# MainBoard.net
KiCad netlist of a schematic drawn in EAGLE
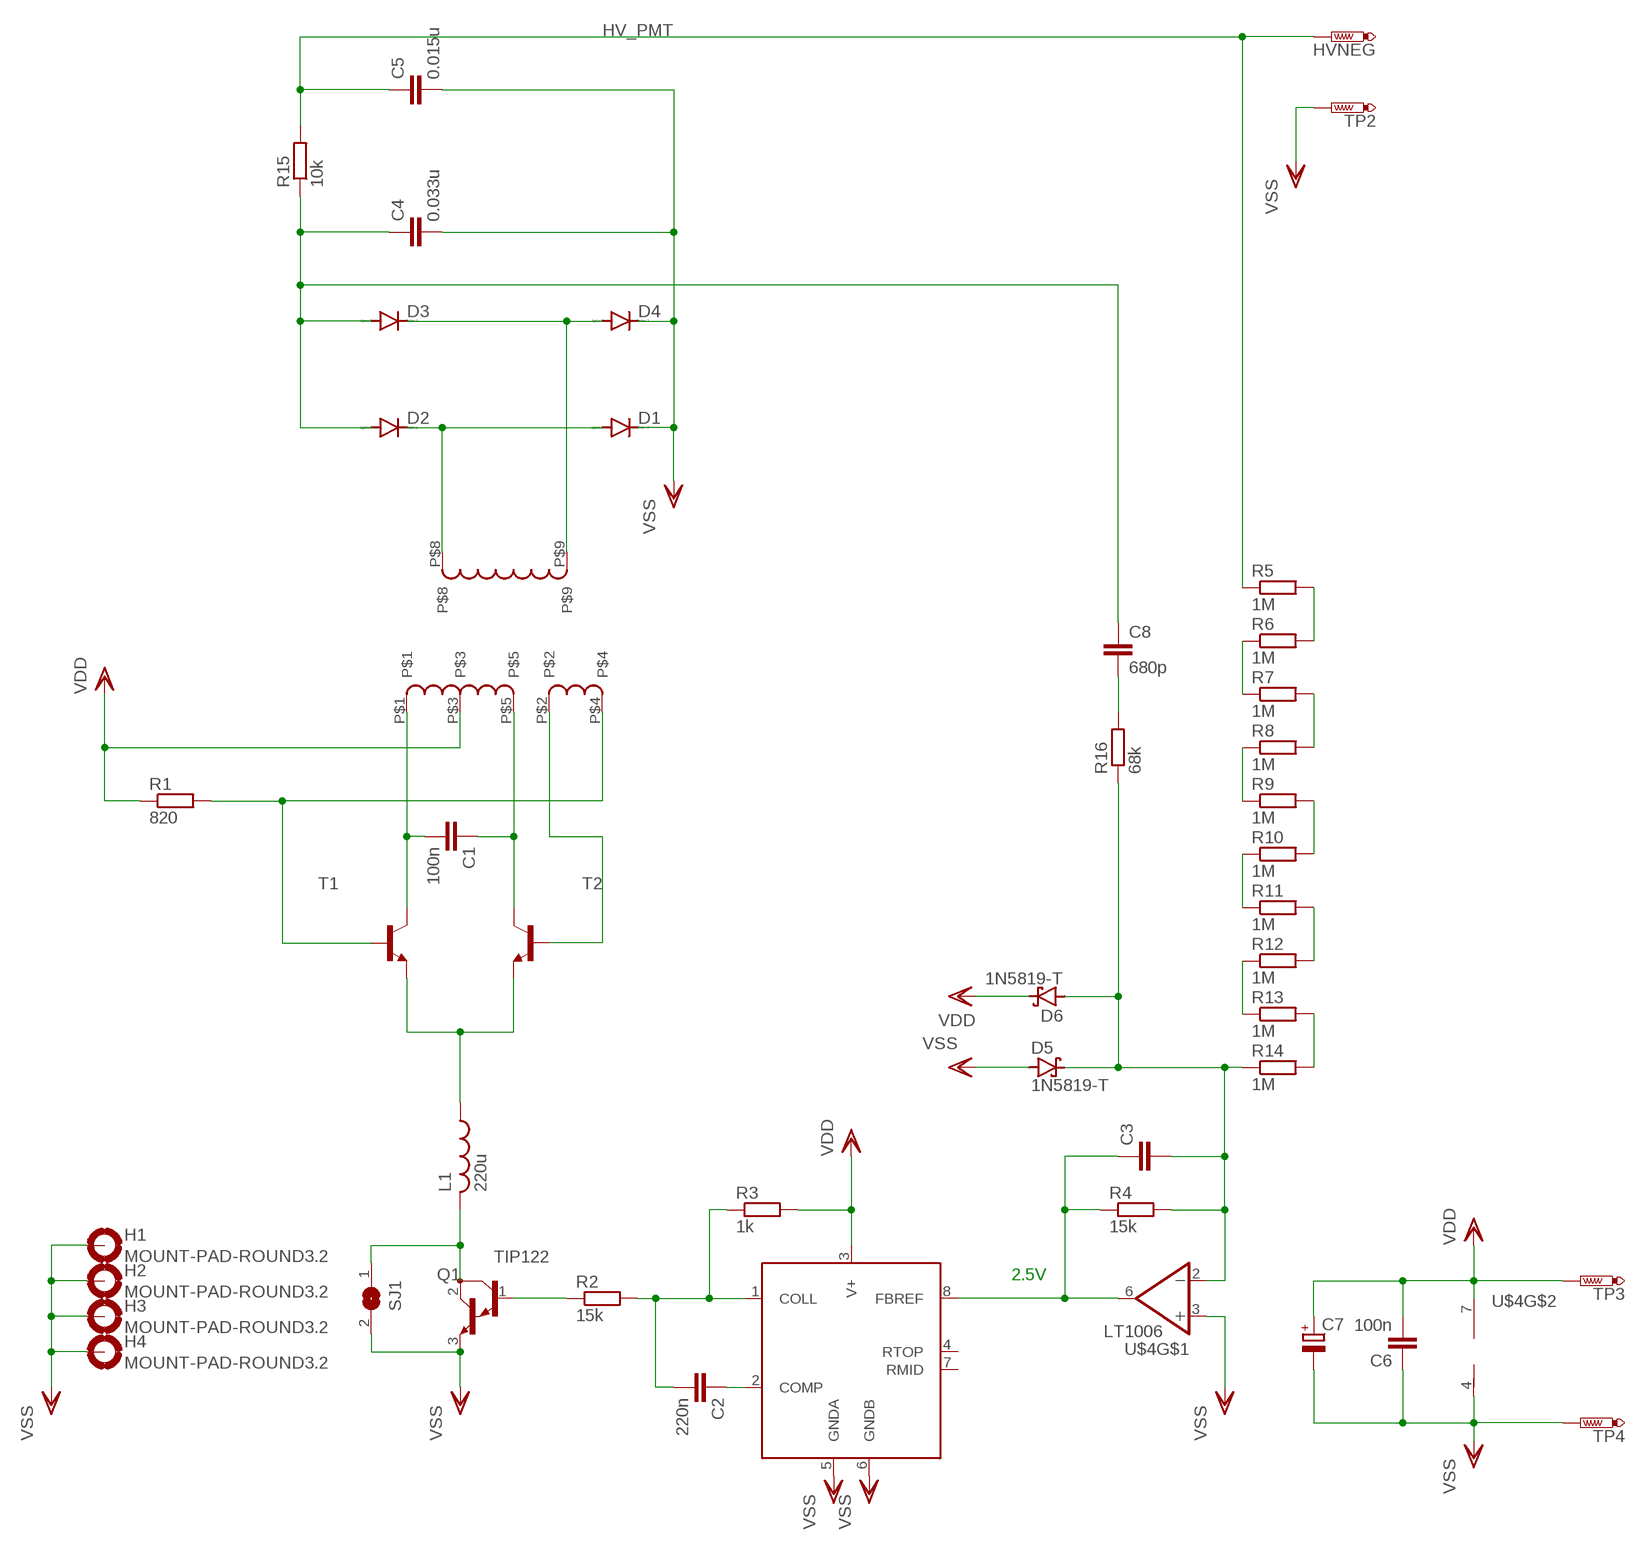
[diagram p0: schematic, sheet 1]

(export (version "E")
  (design (tool "Eeschema 10.0.6"))
  (components
    (comp (ref "C1")
      (value "100n")
      (footprint "eagle-import:C075-032X103")
      (libsource (lib "eagle-import") (part "C-EU075-032X103"))
    )
    (comp (ref "C2")
      (value "220n")
      (footprint "eagle-import:C050-035X075")
      (libsource (lib "eagle-import") (part "C-EU050-035X075"))
    )
    (comp (ref "C3")
      (value "C-EU075-032X103")
      (footprint "eagle-import:C075-032X103")
      (libsource (lib "eagle-import") (part "C-EU075-032X103"))
    )
    (comp (ref "C4")
      (value "0.033u")
      (footprint "eagle-import:C225-087X268")
      (libsource (lib "eagle-import") (part "C-EU225-087X268"))
    )
    (comp (ref "C5")
      (value "0.015u")
      (footprint "eagle-import:C225-087X268")
      (libsource (lib "eagle-import") (part "C-EU225-087X268"))
    )
    (comp (ref "C6")
      (value "100n")
      (footprint "eagle-import:C075-032X103")
      (libsource (lib "eagle-import") (part "C-EU075-032X103"))
    )
    (comp (ref "C7")
      (value "CPOL-EUE2.5-7")
      (footprint "eagle-import:E2,5-7")
      (libsource (lib "eagle-import") (part "CPOL-EUE2.5-7"))
    )
    (comp (ref "C8")
      (value "680p")
      (footprint "eagle-import:C150-064X183")
      (libsource (lib "eagle-import") (part "C-EU150-064X183"))
    )
    (comp (ref "D1")
      (value "DIODE-DO41-10")
      (footprint "eagle-import:DO41-10")
      (libsource (lib "eagle-import") (part "DIODE-DO41-10"))
    )
    (comp (ref "D2")
      (value "DIODE-DO41-10")
      (footprint "eagle-import:DO41-10")
      (libsource (lib "eagle-import") (part "DIODE-DO41-10"))
    )
    (comp (ref "D3")
      (value "DIODE-DO41-10")
      (footprint "eagle-import:DO41-10")
      (libsource (lib "eagle-import") (part "DIODE-DO41-10"))
    )
    (comp (ref "D4")
      (value "DIODE-DO41-10")
      (footprint "eagle-import:DO41-10")
      (libsource (lib "eagle-import") (part "DIODE-DO41-10"))
    )
    (comp (ref "D5")
      (value "1N5819-T")
      (footprint "eagle-import:DO41-7.6")
      (libsource (lib "eagle-import") (part "1N5819-T"))
    )
    (comp (ref "D6")
      (value "1N5819-T")
      (footprint "eagle-import:DO41-7.6")
      (libsource (lib "eagle-import") (part "1N5819-T"))
    )
    (comp (ref "H1")
      (value "MOUNT-PAD-ROUND3.2")
      (footprint "eagle-import:3,2-PAD")
      (libsource (lib "eagle-import") (part "MOUNT-PAD-ROUND3.2"))
    )
    (comp (ref "H2")
      (value "MOUNT-PAD-ROUND3.2")
      (footprint "eagle-import:3,2-PAD")
      (libsource (lib "eagle-import") (part "MOUNT-PAD-ROUND3.2"))
    )
    (comp (ref "H3")
      (value "MOUNT-PAD-ROUND3.2")
      (footprint "eagle-import:3,2-PAD")
      (libsource (lib "eagle-import") (part "MOUNT-PAD-ROUND3.2"))
    )
    (comp (ref "H4")
      (value "MOUNT-PAD-ROUND3.2")
      (footprint "eagle-import:3,2-PAD")
      (libsource (lib "eagle-import") (part "MOUNT-PAD-ROUND3.2"))
    )
    (comp (ref "HVNEG")
      (value "PTR1PAD1-13Y")
      (footprint "eagle-import:P1-13Y")
      (libsource (lib "eagle-import") (part "PTR1PAD1-13Y"))
    )
    (comp (ref "L1")
      (value "220u")
      (footprint "eagle-import:0207_15")
      (libsource (lib "eagle-import") (part "L-US0207/15"))
    )
    (comp (ref "Q1")
      (value "TIP122")
      (footprint "eagle-import:TO220")
      (libsource (lib "eagle-import") (part "TIP122"))
    )
    (comp (ref "R1")
      (value "820")
      (footprint "eagle-import:0207_7")
      (libsource (lib "eagle-import") (part "R-EU_0207/7"))
    )
    (comp (ref "R2")
      (value "15k")
      (footprint "eagle-import:0207_7")
      (libsource (lib "eagle-import") (part "R-EU_0207/7"))
    )
    (comp (ref "R3")
      (value "1k")
      (footprint "eagle-import:0207_7")
      (libsource (lib "eagle-import") (part "R-EU_0207/7"))
    )
    (comp (ref "R4")
      (value "15k")
      (footprint "eagle-import:0207_7")
      (libsource (lib "eagle-import") (part "R-EU_0207/7"))
    )
    (comp (ref "R5")
      (value "1M")
      (footprint "eagle-import:0207_7")
      (libsource (lib "eagle-import") (part "R-EU_0207/7"))
    )
    (comp (ref "R6")
      (value "1M")
      (footprint "eagle-import:0207_7")
      (libsource (lib "eagle-import") (part "R-EU_0207/7"))
    )
    (comp (ref "R7")
      (value "1M")
      (footprint "eagle-import:0207_7")
      (libsource (lib "eagle-import") (part "R-EU_0207/7"))
    )
    (comp (ref "R8")
      (value "1M")
      (footprint "eagle-import:0207_7")
      (libsource (lib "eagle-import") (part "R-EU_0207/7"))
    )
    (comp (ref "R9")
      (value "1M")
      (footprint "eagle-import:0207_7")
      (libsource (lib "eagle-import") (part "R-EU_0207/7"))
    )
    (comp (ref "R10")
      (value "1M")
      (footprint "eagle-import:0207_7")
      (libsource (lib "eagle-import") (part "R-EU_0207/7"))
    )
    (comp (ref "R11")
      (value "1M")
      (footprint "eagle-import:0207_7")
      (libsource (lib "eagle-import") (part "R-EU_0207/7"))
    )
    (comp (ref "R12")
      (value "1M")
      (footprint "eagle-import:0207_7")
      (libsource (lib "eagle-import") (part "R-EU_0207/7"))
    )
    (comp (ref "R13")
      (value "1M")
      (footprint "eagle-import:0207_7")
      (libsource (lib "eagle-import") (part "R-EU_0207/7"))
    )
    (comp (ref "R14")
      (value "1M")
      (footprint "eagle-import:0207_7")
      (libsource (lib "eagle-import") (part "R-EU_0207/7"))
    )
    (comp (ref "R15")
      (value "10k")
      (footprint "eagle-import:0207_7")
      (libsource (lib "eagle-import") (part "R-EU_0207/7"))
    )
    (comp (ref "R16")
      (value "68k")
      (footprint "eagle-import:0207_7")
      (libsource (lib "eagle-import") (part "R-EU_0207/7"))
    )
    (comp (ref "SJ1") (value "SJ") (footprint "eagle-import:SJ") (libsource (lib "eagle-import") (part "SJ")))
    (comp (ref "T1")
      (value "-NPN-TO92-EBC")
      (footprint "eagle-import:TO92-EBC")
      (libsource (lib "eagle-import") (part "-NPN-TO92-EBC"))
    )
    (comp (ref "T2")
      (value "-NPN-TO92-EBC")
      (footprint "eagle-import:TO92-EBC")
      (libsource (lib "eagle-import") (part "-NPN-TO92-EBC"))
    )
    (comp (ref "TP2")
      (value "PTR1PAD1-13Y")
      (footprint "eagle-import:P1-13Y")
      (libsource (lib "eagle-import") (part "PTR1PAD1-13Y"))
    )
    (comp (ref "TP3")
      (value "PTR1PAD1-13Y")
      (footprint "eagle-import:P1-13Y")
      (libsource (lib "eagle-import") (part "PTR1PAD1-13Y"))
    )
    (comp (ref "TP4")
      (value "PTR1PAD1-13Y")
      (footprint "eagle-import:P1-13Y")
      (libsource (lib "eagle-import") (part "PTR1PAD1-13Y"))
    )
    (comp (ref "U$1")
      (value "FL2015")
      (footprint "eagle-import:FL2015-A")
      (libsource (lib "eagle-import") (part "FL2015"))
    )
    (comp (ref "U$3")
      (value "LT1431")
      (footprint "eagle-import:SO08")
      (libsource (lib "eagle-import") (part "LT1431"))
    )
    (comp (ref "U$4")
      (value "LT1006")
      (footprint "eagle-import:SO08")
      (libsource (lib "eagle-import") (part "LT1006"))
    )
  )
  (nets
    (net (code "1") (name "/HV_PMT") (class "Default")
      (node (ref "C5") (pin "1") (pinfunction "1_1") (pintype "passive"))
      (node (ref "HVNEG") (pin "TP") (pinfunction "TP_TP") (pintype "input"))
      (node (ref "R15") (pin "2") (pinfunction "2_2") (pintype "passive"))
      (node (ref "R5") (pin "1") (pinfunction "1_1") (pintype "passive"))
    )
    (net (code "2") (name "Net-(C1-Pad1)") (class "Default")
      (node (ref "C1") (pin "1") (pinfunction "1_1") (pintype "passive"))
      (node (ref "T2") (pin "C") (pinfunction "C_C") (pintype "passive"))
      (node (ref "U$1") (pin "P$5") (pinfunction "P$5_P$5") (pintype "bidirectional"))
    )
    (net (code "3") (name "Net-(C1-Pad2)") (class "Default")
      (node (ref "C1") (pin "2") (pinfunction "2_2") (pintype "passive"))
      (node (ref "T1") (pin "C") (pinfunction "C_C") (pintype "passive"))
      (node (ref "U$1") (pin "P$1") (pinfunction "P$1_P$1") (pintype "bidirectional"))
    )
    (net (code "4") (name "Net-(C4-Pad1)") (class "Default")
      (node (ref "C4") (pin "1") (pinfunction "1_1") (pintype "passive"))
      (node (ref "C8") (pin "1") (pinfunction "1_1") (pintype "passive"))
      (node (ref "D2") (pin "A") (pinfunction "A_A") (pintype "passive"))
      (node (ref "D3") (pin "A") (pinfunction "A_A") (pintype "passive"))
      (node (ref "R15") (pin "1") (pinfunction "1_1") (pintype "passive"))
    )
    (net (code "5") (name "Net-(C8-Pad2)") (class "Default")
      (node (ref "C8") (pin "2") (pinfunction "2_2") (pintype "passive"))
      (node (ref "R16") (pin "2") (pinfunction "2_2") (pintype "passive"))
    )
    (net (code "6") (name "Net-(D1-PadA)") (class "Default")
      (node (ref "D1") (pin "A") (pinfunction "A_A") (pintype "passive"))
      (node (ref "D2") (pin "C") (pinfunction "C_C") (pintype "passive"))
      (node (ref "U$1") (pin "P$8") (pinfunction "P$8_P$8") (pintype "bidirectional"))
    )
    (net (code "7") (name "Net-(D3-PadC)") (class "Default")
      (node (ref "D3") (pin "C") (pinfunction "C_C") (pintype "passive"))
      (node (ref "D4") (pin "A") (pinfunction "A_A") (pintype "passive"))
      (node (ref "U$1") (pin "P$9") (pinfunction "P$9_P$9") (pintype "bidirectional"))
    )
    (net (code "8") (name "Net-(L1-Pad1)") (class "Default")
      (node (ref "L1") (pin "1") (pinfunction "1_1") (pintype "passive"))
      (node (ref "T1") (pin "E") (pinfunction "E_E") (pintype "passive"))
      (node (ref "T2") (pin "E") (pinfunction "E_E") (pintype "passive"))
    )
    (net (code "9") (name "Net-(Q1-B)") (class "Default")
      (node (ref "Q1") (pin "1") (pinfunction "B_1") (pintype "passive"))
      (node (ref "R2") (pin "1") (pinfunction "1_1") (pintype "passive"))
    )
    (net (code "10") (name "Net-(Q1-C)") (class "Default")
      (node (ref "L1") (pin "2") (pinfunction "2_2") (pintype "passive"))
      (node (ref "Q1") (pin "2") (pinfunction "C_2") (pintype "passive"))
      (node (ref "SJ1") (pin "1") (pinfunction "1_1") (pintype "passive"))
    )
    (net (code "11") (name "Net-(R1-Pad2)") (class "Default")
      (node (ref "R1") (pin "2") (pinfunction "2_2") (pintype "passive"))
      (node (ref "T1") (pin "B") (pinfunction "B_B") (pintype "passive"))
      (node (ref "U$1") (pin "P$4") (pinfunction "P$4_P$4") (pintype "bidirectional"))
    )
    (net (code "12") (name "Net-(R5-Pad2)") (class "Default")
      (node (ref "R5") (pin "2") (pinfunction "2_2") (pintype "passive"))
      (node (ref "R6") (pin "2") (pinfunction "2_2") (pintype "passive"))
    )
    (net (code "13") (name "Net-(R6-Pad1)") (class "Default")
      (node (ref "R6") (pin "1") (pinfunction "1_1") (pintype "passive"))
      (node (ref "R7") (pin "1") (pinfunction "1_1") (pintype "passive"))
    )
    (net (code "14") (name "Net-(R7-Pad2)") (class "Default")
      (node (ref "R7") (pin "2") (pinfunction "2_2") (pintype "passive"))
      (node (ref "R8") (pin "2") (pinfunction "2_2") (pintype "passive"))
    )
    (net (code "15") (name "Net-(R8-Pad1)") (class "Default")
      (node (ref "R8") (pin "1") (pinfunction "1_1") (pintype "passive"))
      (node (ref "R9") (pin "1") (pinfunction "1_1") (pintype "passive"))
    )
    (net (code "16") (name "Net-(R10-Pad1)") (class "Default")
      (node (ref "R10") (pin "1") (pinfunction "1_1") (pintype "passive"))
      (node (ref "R11") (pin "1") (pinfunction "1_1") (pintype "passive"))
    )
    (net (code "17") (name "Net-(R10-Pad2)") (class "Default")
      (node (ref "R10") (pin "2") (pinfunction "2_2") (pintype "passive"))
      (node (ref "R9") (pin "2") (pinfunction "2_2") (pintype "passive"))
    )
    (net (code "18") (name "Net-(R11-Pad2)") (class "Default")
      (node (ref "R11") (pin "2") (pinfunction "2_2") (pintype "passive"))
      (node (ref "R12") (pin "2") (pinfunction "2_2") (pintype "passive"))
    )
    (net (code "19") (name "Net-(R12-Pad1)") (class "Default")
      (node (ref "R12") (pin "1") (pinfunction "1_1") (pintype "passive"))
      (node (ref "R13") (pin "1") (pinfunction "1_1") (pintype "passive"))
    )
    (net (code "20") (name "Net-(R13-Pad2)") (class "Default")
      (node (ref "R13") (pin "2") (pinfunction "2_2") (pintype "passive"))
      (node (ref "R14") (pin "2") (pinfunction "2_2") (pintype "passive"))
    )
    (net (code "21") (name "Net-(T2-PadB)") (class "Default")
      (node (ref "T2") (pin "B") (pinfunction "B_B") (pintype "passive"))
      (node (ref "U$1") (pin "P$2") (pinfunction "P$2_P$2") (pintype "bidirectional"))
    )
    (net (code "22") (name "Net-(U$3-COLL)") (class "Default")
      (node (ref "C2") (pin "2") (pinfunction "2_2") (pintype "passive"))
      (node (ref "R2") (pin "2") (pinfunction "2_2") (pintype "passive"))
      (node (ref "R3") (pin "1") (pinfunction "1_1") (pintype "passive"))
      (node (ref "U$3") (pin "1") (pinfunction "COLL_1") (pintype "bidirectional"))
    )
    (net (code "23") (name "Net-(U$3-COMP)") (class "Default")
      (node (ref "C2") (pin "1") (pinfunction "1_1") (pintype "passive"))
      (node (ref "U$3") (pin "2") (pinfunction "COMP_2") (pintype "bidirectional"))
    )
    (net (code "24") (name "Net-(U$3-FBREF)") (class "Default")
      (node (ref "C3") (pin "1") (pinfunction "1_1") (pintype "passive"))
      (node (ref "R4") (pin "1") (pinfunction "1_1") (pintype "passive"))
      (node (ref "U$3") (pin "8") (pinfunction "FBREF_8") (pintype "bidirectional"))
      (node (ref "U$4") (pin "6") (pinfunction "OUT_6") (pintype "output"))
    )
    (net (code "25") (name "Net-(U$4A--IN)") (class "Default")
      (node (ref "C3") (pin "2") (pinfunction "2_2") (pintype "passive"))
      (node (ref "D5") (pin "C") (pinfunction "C_C") (pintype "passive"))
      (node (ref "D6") (pin "A") (pinfunction "A_A") (pintype "passive"))
      (node (ref "R14") (pin "1") (pinfunction "1_1") (pintype "passive"))
      (node (ref "R16") (pin "1") (pinfunction "1_1") (pintype "passive"))
      (node (ref "R4") (pin "2") (pinfunction "2_2") (pintype "passive"))
      (node (ref "U$4") (pin "2") (pinfunction "-IN_2") (pintype "input"))
    )
    (net (code "26") (name "VDD") (class "Default")
      (node (ref "C6") (pin "2") (pinfunction "2_2") (pintype "passive"))
      (node (ref "C7") (pin "+") (pinfunction "+_+") (pintype "passive"))
      (node (ref "D6") (pin "C") (pinfunction "C_C") (pintype "passive"))
      (node (ref "R1") (pin "1") (pinfunction "1_1") (pintype "passive"))
      (node (ref "R3") (pin "2") (pinfunction "2_2") (pintype "passive"))
      (node (ref "TP3") (pin "TP") (pinfunction "TP_TP") (pintype "input"))
      (node (ref "U$1") (pin "P$3") (pinfunction "P$3_P$3") (pintype "bidirectional"))
      (node (ref "U$3") (pin "3") (pinfunction "V+_3") (pintype "bidirectional"))
      (node (ref "U$4") (pin "7") (pinfunction "V+_7") (pintype "power_in"))
    )
    (net (code "27") (name "VSS") (class "Default")
      (node (ref "C4") (pin "2") (pinfunction "2_2") (pintype "passive"))
      (node (ref "C5") (pin "2") (pinfunction "2_2") (pintype "passive"))
      (node (ref "C6") (pin "1") (pinfunction "1_1") (pintype "passive"))
      (node (ref "C7") (pin "-") (pinfunction "-_-") (pintype "passive"))
      (node (ref "D1") (pin "C") (pinfunction "C_C") (pintype "passive"))
      (node (ref "D4") (pin "C") (pinfunction "C_C") (pintype "passive"))
      (node (ref "D5") (pin "A") (pinfunction "A_A") (pintype "passive"))
      (node (ref "H1") (pin "B3,2") (pinfunction "MOUNT_B3,2") (pintype "passive"))
      (node (ref "H2") (pin "B3,2") (pinfunction "MOUNT_B3,2") (pintype "passive"))
      (node (ref "H3") (pin "B3,2") (pinfunction "MOUNT_B3,2") (pintype "passive"))
      (node (ref "H4") (pin "B3,2") (pinfunction "MOUNT_B3,2") (pintype "passive"))
      (node (ref "Q1") (pin "3") (pinfunction "E_3") (pintype "passive"))
      (node (ref "SJ1") (pin "2") (pinfunction "2_2") (pintype "passive"))
      (node (ref "TP2") (pin "TP") (pinfunction "TP_TP") (pintype "input"))
      (node (ref "TP4") (pin "TP") (pinfunction "TP_TP") (pintype "input"))
      (node (ref "U$3") (pin "5") (pinfunction "GNDA_5") (pintype "bidirectional"))
      (node (ref "U$3") (pin "6") (pinfunction "GNDB_6") (pintype "bidirectional"))
      (node (ref "U$4") (pin "3") (pinfunction "+IN_3") (pintype "input"))
      (node (ref "U$4") (pin "4") (pinfunction "V-_4") (pintype "power_in"))
    )
    (net (code "28") (name "unconnected-(U$3-RMID-Pad7)") (class "Default")
      (node (ref "U$3") (pin "7") (pinfunction "RMID_7") (pintype "bidirectional"))
    )
    (net (code "29") (name "unconnected-(U$3-RTOP-Pad4)") (class "Default")
      (node (ref "U$3") (pin "4") (pinfunction "RTOP_4") (pintype "bidirectional"))
    )
  )
)
